# TES1.net
KiCad netlist of a schematic drawn in EAGLE
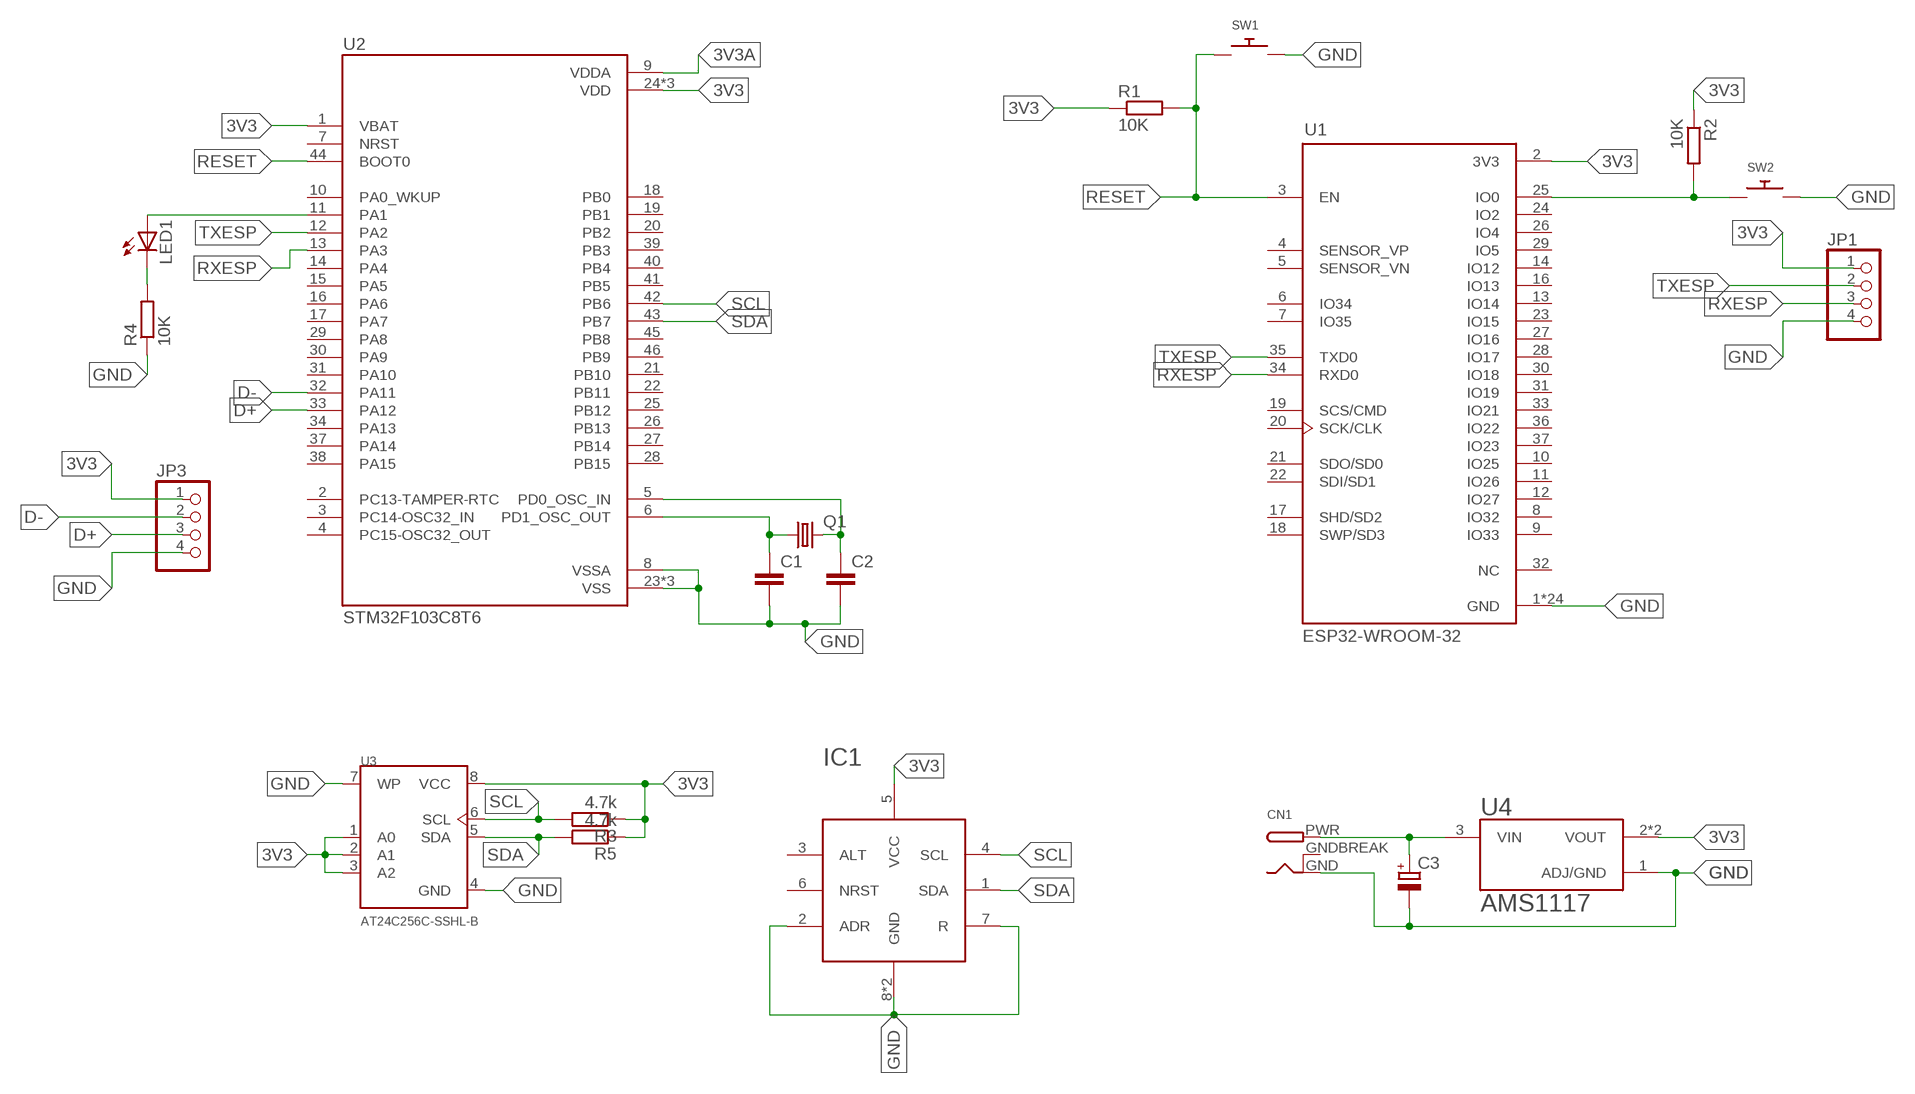
[diagram p0: schematic, sheet 1]

(export (version "E")
  (design (tool "Eeschema 10.0.6"))
  (components
    (comp (ref "C1")
      (value "C-EUC0805")
      (footprint "eagle-import:C0805")
      (libsource (lib "eagle-import") (part "C-EUC0805"))
    )
    (comp (ref "C2")
      (value "C-EUC0805")
      (footprint "eagle-import:C0805")
      (libsource (lib "eagle-import") (part "C-EUC0805"))
    )
    (comp (ref "C3")
      (value "CPOL-EU150CLZ-0810")
      (footprint "eagle-import:150CLZ-0810")
      (libsource (lib "eagle-import") (part "CPOL-EU150CLZ-0810"))
    )
    (comp (ref "CN1")
      (value "DCBARRELPTH")
      (footprint "eagle-import:DCJACK_2MM_PTH")
      (libsource (lib "eagle-import") (part "DCBARRELPTH"))
    )
    (comp (ref "IC1")
      (value "SHT31")
      (footprint "eagle-import:SON50P250X250X90-9T110X180N")
      (fields (field (name "MF") "Sensirion AG"))
      (libsource (lib "eagle-import") (part "SHT31"))
    )
    (comp (ref "JP1")
      (value "PINHD-1X4")
      (footprint "eagle-import:1X04")
      (libsource (lib "eagle-import") (part "PINHD-1X4"))
    )
    (comp (ref "JP3")
      (value "PINHD-1X4")
      (footprint "eagle-import:1X04")
      (libsource (lib "eagle-import") (part "PINHD-1X4"))
    )
    (comp (ref "LED1")
      (value "LEDCHIP-LED0805")
      (footprint "eagle-import:CHIP-LED0805")
      (libsource (lib "eagle-import") (part "LEDCHIP-LED0805"))
    )
    (comp (ref "Q1")
      (value "CRYSTALHC49U-V")
      (footprint "eagle-import:HC49U-V")
      (libsource (lib "eagle-import") (part "CRYSTALHC49U-V"))
    )
    (comp (ref "R1")
      (value "10K")
      (footprint "eagle-import:R0805")
      (libsource (lib "eagle-import") (part "R-EU_R0805"))
    )
    (comp (ref "R2")
      (value "10K")
      (footprint "eagle-import:R0805")
      (libsource (lib "eagle-import") (part "R-EU_R0805"))
    )
    (comp (ref "R3")
      (value "4.7k")
      (footprint "eagle-import:R0805")
      (libsource (lib "eagle-import") (part "R-EU_R0805"))
    )
    (comp (ref "R4")
      (value "10K")
      (footprint "eagle-import:R0805")
      (libsource (lib "eagle-import") (part "R-EU_R0805"))
    )
    (comp (ref "R5")
      (value "4.7k")
      (footprint "eagle-import:R0805")
      (libsource (lib "eagle-import") (part "R-EU_R0805"))
    )
    (comp (ref "SW1")
      (value "SWITCH_PUSHBUTTONC&K_KSS")
      (footprint "eagle-import:BTN_CK_KSS")
      (libsource (lib "eagle-import") (part "SWITCH_PUSHBUTTONC&K_KSS"))
    )
    (comp (ref "SW2")
      (value "SWITCH_PUSHBUTTONC&K_KSS")
      (footprint "eagle-import:BTN_CK_KSS")
      (libsource (lib "eagle-import") (part "SWITCH_PUSHBUTTONC&K_KSS"))
    )
    (comp (ref "U1")
      (value "ESP32-WROOM-32")
      (footprint "eagle-import:MODULE_ESP32-WROOM-32")
      (fields (field (name "MF") "Espressif Systems"))
      (libsource (lib "eagle-import") (part "ESP32-WROOM-32"))
    )
    (comp (ref "U2")
      (value "STM32F103C8T6")
      (footprint "eagle-import:QFP50P900X900X160-48N")
      (fields (field (name "MF") "STMicroelectronics"))
      (libsource (lib "eagle-import") (part "STM32F103C8T6"))
    )
    (comp (ref "U3")
      (value "AT24C256C-SSHL-B")
      (footprint "eagle-import:SOIC127P600X175-8N")
      (fields (field (name "MF") "Microchip"))
      (libsource (lib "eagle-import") (part "AT24C256C-SSHL-B"))
    )
    (comp (ref "U4")
      (value "AMS1117")
      (footprint "eagle-import:SOT229P700X180-4N")
      (fields (field (name "MF") "Advanced Monolithic Systems"))
      (libsource (lib "eagle-import") (part "AMS1117"))
    )
  )
  (nets
    (net (code "1") (name "/GNDBREAK") (class "Default")
      (node (ref "CN1") (pin "GNDBREAK") (pinfunction "GNDBREAK_GNDBREAK") (pintype "power_in"))
    )
    (net (code "2") (name "3V3") (class "Default")
      (node (ref "IC1") (pin "5") (pinfunction "VCC_5") (pintype "bidirectional"))
      (node (ref "JP1") (pin "1") (pinfunction "1_1") (pintype "passive"))
      (node (ref "JP3") (pin "1") (pinfunction "1_1") (pintype "passive"))
      (node (ref "R1") (pin "1") (pinfunction "1_1") (pintype "passive"))
      (node (ref "R2") (pin "1") (pinfunction "1_1") (pintype "passive"))
      (node (ref "R3") (pin "1") (pinfunction "1_1") (pintype "passive"))
      (node (ref "R5") (pin "1") (pinfunction "1_1") (pintype "passive"))
      (node (ref "U1") (pin "2") (pinfunction "3V3_2") (pintype "power_in"))
      (node (ref "U2") (pin "1") (pinfunction "VBAT_1") (pintype "bidirectional"))
      (node (ref "U2") (pin "24") (pinfunction "VDD_24") (pintype "power_in"))
      (node (ref "U2") (pin "36") (pinfunction "VDD_36") (pintype "power_in"))
      (node (ref "U2") (pin "48") (pinfunction "VDD_48") (pintype "power_in"))
      (node (ref "U3") (pin "1") (pinfunction "A0_1") (pintype "input"))
      (node (ref "U3") (pin "2") (pinfunction "A1_2") (pintype "input"))
      (node (ref "U3") (pin "3") (pinfunction "A2_3") (pintype "input"))
      (node (ref "U3") (pin "8") (pinfunction "VCC_8") (pintype "power_in"))
      (node (ref "U4") (pin "2") (pinfunction "VOUT_2") (pintype "output"))
      (node (ref "U4") (pin "4") (pinfunction "VOUT_4") (pintype "output"))
    )
    (net (code "3") (name "3V3A") (class "Default")
      (node (ref "U2") (pin "9") (pinfunction "VDDA_9") (pintype "power_in"))
    )
    (net (code "4") (name "D+") (class "Default")
      (node (ref "JP3") (pin "3") (pinfunction "3_3") (pintype "passive"))
      (node (ref "U2") (pin "33") (pinfunction "PA12_33") (pintype "bidirectional"))
    )
    (net (code "5") (name "D-") (class "Default")
      (node (ref "JP3") (pin "2") (pinfunction "2_2") (pintype "passive"))
      (node (ref "U2") (pin "32") (pinfunction "PA11_32") (pintype "bidirectional"))
    )
    (net (code "6") (name "GND") (class "Default")
      (node (ref "C1") (pin "2") (pinfunction "2_2") (pintype "passive"))
      (node (ref "C2") (pin "2") (pinfunction "2_2") (pintype "passive"))
      (node (ref "C3") (pin "-") (pinfunction "-_-") (pintype "passive"))
      (node (ref "CN1") (pin "GND") (pinfunction "GND_GND") (pintype "power_in"))
      (node (ref "IC1") (pin "2") (pinfunction "ADR_2") (pintype "bidirectional"))
      (node (ref "IC1") (pin "7") (pinfunction "R_7") (pintype "bidirectional"))
      (node (ref "IC1") (pin "8") (pinfunction "GND_8") (pintype "bidirectional"))
      (node (ref "IC1") (pin "9") (pinfunction "GND_9") (pintype "bidirectional"))
      (node (ref "JP1") (pin "4") (pinfunction "4_4") (pintype "passive"))
      (node (ref "JP3") (pin "4") (pinfunction "4_4") (pintype "passive"))
      (node (ref "R4") (pin "1") (pinfunction "1_1") (pintype "passive"))
      (node (ref "SW1") (pin "P$2") (pinfunction "P$2_P$2") (pintype "passive"))
      (node (ref "SW2") (pin "P$2") (pinfunction "P$2_P$2") (pintype "passive"))
      (node (ref "U1") (pin "1") (pinfunction "GND_1") (pintype "power_in"))
      (node (ref "U1") (pin "15") (pinfunction "GND_15") (pintype "power_in"))
      (node (ref "U1") (pin "38") (pinfunction "GND_38") (pintype "power_in"))
      (node (ref "U1") (pin "39_1") (pinfunction "GND_39_1") (pintype "power_in"))
      (node (ref "U1") (pin "39_10") (pinfunction "GND_39_10") (pintype "power_in"))
      (node (ref "U1") (pin "39_11") (pinfunction "GND_39_11") (pintype "power_in"))
      (node (ref "U1") (pin "39_12") (pinfunction "GND_39_12") (pintype "power_in"))
      (node (ref "U1") (pin "39_13") (pinfunction "GND_39_13") (pintype "power_in"))
      (node (ref "U1") (pin "39_14") (pinfunction "GND_39_14") (pintype "power_in"))
      (node (ref "U1") (pin "39_15") (pinfunction "GND_39_15") (pintype "power_in"))
      (node (ref "U1") (pin "39_16") (pinfunction "GND_39_16") (pintype "power_in"))
      (node (ref "U1") (pin "39_17") (pinfunction "GND_39_17") (pintype "power_in"))
      (node (ref "U1") (pin "39_18") (pinfunction "GND_39_18") (pintype "power_in"))
      (node (ref "U1") (pin "39_19") (pinfunction "GND_39_19") (pintype "power_in"))
      (node (ref "U1") (pin "39_2") (pinfunction "GND_39_2") (pintype "power_in"))
      (node (ref "U1") (pin "39_20") (pinfunction "GND_39_20") (pintype "power_in"))
      (node (ref "U1") (pin "39_21") (pinfunction "GND_39_21") (pintype "power_in"))
      (node (ref "U1") (pin "39_3") (pinfunction "GND_39_3") (pintype "power_in"))
      (node (ref "U1") (pin "39_4") (pinfunction "GND_39_4") (pintype "power_in"))
      (node (ref "U1") (pin "39_5") (pinfunction "GND_39_5") (pintype "power_in"))
      (node (ref "U1") (pin "39_6") (pinfunction "GND_39_6") (pintype "power_in"))
      (node (ref "U1") (pin "39_7") (pinfunction "GND_39_7") (pintype "power_in"))
      (node (ref "U1") (pin "39_8") (pinfunction "GND_39_8") (pintype "power_in"))
      (node (ref "U1") (pin "39_9") (pinfunction "GND_39_9") (pintype "power_in"))
      (node (ref "U2") (pin "23") (pinfunction "VSS_23") (pintype "power_in"))
      (node (ref "U2") (pin "35") (pinfunction "VSS_35") (pintype "power_in"))
      (node (ref "U2") (pin "47") (pinfunction "VSS_47") (pintype "power_in"))
      (node (ref "U2") (pin "8") (pinfunction "VSSA_8") (pintype "power_in"))
      (node (ref "U3") (pin "4") (pinfunction "GND_4") (pintype "power_in"))
      (node (ref "U3") (pin "7") (pinfunction "WP_7") (pintype "input"))
      (node (ref "U4") (pin "1") (pinfunction "ADJ/GND_1") (pintype "power_in"))
    )
    (net (code "7") (name "Net-(LED1-PadC)") (class "Default")
      (node (ref "LED1") (pin "C") (pinfunction "C_C") (pintype "passive"))
      (node (ref "R4") (pin "2") (pinfunction "2_2") (pintype "passive"))
    )
    (net (code "8") (name "Net-(U1-IO0)") (class "Default")
      (node (ref "R2") (pin "2") (pinfunction "2_2") (pintype "passive"))
      (node (ref "SW2") (pin "P$1") (pinfunction "P$1_P$1") (pintype "passive"))
      (node (ref "U1") (pin "25") (pinfunction "IO0_25") (pintype "bidirectional"))
    )
    (net (code "9") (name "Net-(U2-PA1)") (class "Default")
      (node (ref "LED1") (pin "A") (pinfunction "A_A") (pintype "passive"))
      (node (ref "U2") (pin "11") (pinfunction "PA1_11") (pintype "bidirectional"))
    )
    (net (code "10") (name "Net-(U2-PD0_OSC_IN)") (class "Default")
      (node (ref "C2") (pin "1") (pinfunction "1_1") (pintype "passive"))
      (node (ref "Q1") (pin "2") (pinfunction "2_2") (pintype "passive"))
      (node (ref "U2") (pin "5") (pinfunction "PD0_OSC_IN_5") (pintype "bidirectional"))
    )
    (net (code "11") (name "Net-(U2-PD1_OSC_OUT)") (class "Default")
      (node (ref "C1") (pin "1") (pinfunction "1_1") (pintype "passive"))
      (node (ref "Q1") (pin "1") (pinfunction "1_1") (pintype "passive"))
      (node (ref "U2") (pin "6") (pinfunction "PD1_OSC_OUT_6") (pintype "bidirectional"))
    )
    (net (code "12") (name "Net-(U4-VIN)") (class "Default")
      (node (ref "C3") (pin "+") (pinfunction "+_+") (pintype "passive"))
      (node (ref "CN1") (pin "PWR") (pinfunction "PWR_PWR") (pintype "power_in"))
      (node (ref "U4") (pin "3") (pinfunction "VIN_3") (pintype "input"))
    )
    (net (code "13") (name "RESET") (class "Default")
      (node (ref "R1") (pin "2") (pinfunction "2_2") (pintype "passive"))
      (node (ref "SW1") (pin "P$1") (pinfunction "P$1_P$1") (pintype "passive"))
      (node (ref "U1") (pin "3") (pinfunction "EN_3") (pintype "input"))
      (node (ref "U2") (pin "44") (pinfunction "BOOT0_44") (pintype "input"))
    )
    (net (code "14") (name "RXESP") (class "Default")
      (node (ref "JP1") (pin "3") (pinfunction "3_3") (pintype "passive"))
      (node (ref "U1") (pin "34") (pinfunction "RXD0_34") (pintype "bidirectional"))
      (node (ref "U2") (pin "13") (pinfunction "PA3_13") (pintype "bidirectional"))
    )
    (net (code "15") (name "SCL") (class "Default")
      (node (ref "IC1") (pin "4") (pinfunction "SCL_4") (pintype "bidirectional"))
      (node (ref "R3") (pin "2") (pinfunction "2_2") (pintype "passive"))
      (node (ref "U2") (pin "42") (pinfunction "PB6_42") (pintype "bidirectional"))
      (node (ref "U3") (pin "6") (pinfunction "SCL_6") (pintype "input"))
    )
    (net (code "16") (name "SDA") (class "Default")
      (node (ref "IC1") (pin "1") (pinfunction "SDA_1") (pintype "bidirectional"))
      (node (ref "R5") (pin "2") (pinfunction "2_2") (pintype "passive"))
      (node (ref "U2") (pin "43") (pinfunction "PB7_43") (pintype "bidirectional"))
      (node (ref "U3") (pin "5") (pinfunction "SDA_5") (pintype "bidirectional"))
    )
    (net (code "17") (name "TXESP") (class "Default")
      (node (ref "JP1") (pin "2") (pinfunction "2_2") (pintype "passive"))
      (node (ref "U1") (pin "35") (pinfunction "TXD0_35") (pintype "bidirectional"))
      (node (ref "U2") (pin "12") (pinfunction "PA2_12") (pintype "bidirectional"))
    )
    (net (code "18") (name "unconnected-(IC1-ALT-Pad3)") (class "Default")
      (node (ref "IC1") (pin "3") (pinfunction "ALT_3") (pintype "bidirectional"))
    )
    (net (code "19") (name "unconnected-(IC1-NRST-Pad6)") (class "Default")
      (node (ref "IC1") (pin "6") (pinfunction "NRST_6") (pintype "bidirectional"))
    )
    (net (code "20") (name "unconnected-(U1-IO2-Pad24)") (class "Default")
      (node (ref "U1") (pin "24") (pinfunction "IO2_24") (pintype "bidirectional"))
    )
    (net (code "21") (name "unconnected-(U1-IO4-Pad26)") (class "Default")
      (node (ref "U1") (pin "26") (pinfunction "IO4_26") (pintype "bidirectional"))
    )
    (net (code "22") (name "unconnected-(U1-IO5-Pad29)") (class "Default")
      (node (ref "U1") (pin "29") (pinfunction "IO5_29") (pintype "bidirectional"))
    )
    (net (code "23") (name "unconnected-(U1-IO12-Pad14)") (class "Default")
      (node (ref "U1") (pin "14") (pinfunction "IO12_14") (pintype "bidirectional"))
    )
    (net (code "24") (name "unconnected-(U1-IO13-Pad16)") (class "Default")
      (node (ref "U1") (pin "16") (pinfunction "IO13_16") (pintype "bidirectional"))
    )
    (net (code "25") (name "unconnected-(U1-IO14-Pad13)") (class "Default")
      (node (ref "U1") (pin "13") (pinfunction "IO14_13") (pintype "bidirectional"))
    )
    (net (code "26") (name "unconnected-(U1-IO15-Pad23)") (class "Default")
      (node (ref "U1") (pin "23") (pinfunction "IO15_23") (pintype "bidirectional"))
    )
    (net (code "27") (name "unconnected-(U1-IO16-Pad27)") (class "Default")
      (node (ref "U1") (pin "27") (pinfunction "IO16_27") (pintype "bidirectional"))
    )
    (net (code "28") (name "unconnected-(U1-IO17-Pad28)") (class "Default")
      (node (ref "U1") (pin "28") (pinfunction "IO17_28") (pintype "bidirectional"))
    )
    (net (code "29") (name "unconnected-(U1-IO18-Pad30)") (class "Default")
      (node (ref "U1") (pin "30") (pinfunction "IO18_30") (pintype "bidirectional"))
    )
    (net (code "30") (name "unconnected-(U1-IO19-Pad31)") (class "Default")
      (node (ref "U1") (pin "31") (pinfunction "IO19_31") (pintype "bidirectional"))
    )
    (net (code "31") (name "unconnected-(U1-IO21-Pad33)") (class "Default")
      (node (ref "U1") (pin "33") (pinfunction "IO21_33") (pintype "bidirectional"))
    )
    (net (code "32") (name "unconnected-(U1-IO22-Pad36)") (class "Default")
      (node (ref "U1") (pin "36") (pinfunction "IO22_36") (pintype "bidirectional"))
    )
    (net (code "33") (name "unconnected-(U1-IO23-Pad37)") (class "Default")
      (node (ref "U1") (pin "37") (pinfunction "IO23_37") (pintype "bidirectional"))
    )
    (net (code "34") (name "unconnected-(U1-IO25-Pad10)") (class "Default")
      (node (ref "U1") (pin "10") (pinfunction "IO25_10") (pintype "bidirectional"))
    )
    (net (code "35") (name "unconnected-(U1-IO26-Pad11)") (class "Default")
      (node (ref "U1") (pin "11") (pinfunction "IO26_11") (pintype "bidirectional"))
    )
    (net (code "36") (name "unconnected-(U1-IO27-Pad12)") (class "Default")
      (node (ref "U1") (pin "12") (pinfunction "IO27_12") (pintype "bidirectional"))
    )
    (net (code "37") (name "unconnected-(U1-IO32-Pad8)") (class "Default")
      (node (ref "U1") (pin "8") (pinfunction "IO32_8") (pintype "bidirectional"))
    )
    (net (code "38") (name "unconnected-(U1-IO33-Pad9)") (class "Default")
      (node (ref "U1") (pin "9") (pinfunction "IO33_9") (pintype "bidirectional"))
    )
    (net (code "39") (name "unconnected-(U1-IO34-Pad6)") (class "Default")
      (node (ref "U1") (pin "6") (pinfunction "IO34_6") (pintype "input"))
    )
    (net (code "40") (name "unconnected-(U1-IO35-Pad7)") (class "Default")
      (node (ref "U1") (pin "7") (pinfunction "IO35_7") (pintype "input"))
    )
    (net (code "41") (name "unconnected-(U1-NC-Pad32)") (class "Default")
      (node (ref "U1") (pin "32") (pinfunction "NC_32") (pintype "no_connect"))
    )
    (net (code "42") (name "unconnected-(U1-SCK{slash}CLK-Pad20)") (class "Default")
      (node (ref "U1") (pin "20") (pinfunction "SCK/CLK_20") (pintype "bidirectional"))
    )
    (net (code "43") (name "unconnected-(U1-SCS{slash}CMD-Pad19)") (class "Default")
      (node (ref "U1") (pin "19") (pinfunction "SCS/CMD_19") (pintype "bidirectional"))
    )
    (net (code "44") (name "unconnected-(U1-SDI{slash}SD1-Pad22)") (class "Default")
      (node (ref "U1") (pin "22") (pinfunction "SDI/SD1_22") (pintype "bidirectional"))
    )
    (net (code "45") (name "unconnected-(U1-SDO{slash}SD0-Pad21)") (class "Default")
      (node (ref "U1") (pin "21") (pinfunction "SDO/SD0_21") (pintype "bidirectional"))
    )
    (net (code "46") (name "unconnected-(U1-SENSOR_VN-Pad5)") (class "Default")
      (node (ref "U1") (pin "5") (pinfunction "SENSOR_VN_5") (pintype "input"))
    )
    (net (code "47") (name "unconnected-(U1-SENSOR_VP-Pad4)") (class "Default")
      (node (ref "U1") (pin "4") (pinfunction "SENSOR_VP_4") (pintype "input"))
    )
    (net (code "48") (name "unconnected-(U1-SHD{slash}SD2-Pad17)") (class "Default")
      (node (ref "U1") (pin "17") (pinfunction "SHD/SD2_17") (pintype "bidirectional"))
    )
    (net (code "49") (name "unconnected-(U1-SWP{slash}SD3-Pad18)") (class "Default")
      (node (ref "U1") (pin "18") (pinfunction "SWP/SD3_18") (pintype "bidirectional"))
    )
    (net (code "50") (name "unconnected-(U2-NRST-Pad7)") (class "Default")
      (node (ref "U2") (pin "7") (pinfunction "NRST_7") (pintype "input"))
    )
    (net (code "51") (name "unconnected-(U2-PA0_WKUP-Pad10)") (class "Default")
      (node (ref "U2") (pin "10") (pinfunction "PA0_WKUP_10") (pintype "bidirectional"))
    )
    (net (code "52") (name "unconnected-(U2-PA4-Pad14)") (class "Default")
      (node (ref "U2") (pin "14") (pinfunction "PA4_14") (pintype "bidirectional"))
    )
    (net (code "53") (name "unconnected-(U2-PA5-Pad15)") (class "Default")
      (node (ref "U2") (pin "15") (pinfunction "PA5_15") (pintype "bidirectional"))
    )
    (net (code "54") (name "unconnected-(U2-PA6-Pad16)") (class "Default")
      (node (ref "U2") (pin "16") (pinfunction "PA6_16") (pintype "bidirectional"))
    )
    (net (code "55") (name "unconnected-(U2-PA7-Pad17)") (class "Default")
      (node (ref "U2") (pin "17") (pinfunction "PA7_17") (pintype "bidirectional"))
    )
    (net (code "56") (name "unconnected-(U2-PA8-Pad29)") (class "Default")
      (node (ref "U2") (pin "29") (pinfunction "PA8_29") (pintype "bidirectional"))
    )
    (net (code "57") (name "unconnected-(U2-PA9-Pad30)") (class "Default")
      (node (ref "U2") (pin "30") (pinfunction "PA9_30") (pintype "bidirectional"))
    )
    (net (code "58") (name "unconnected-(U2-PA10-Pad31)") (class "Default")
      (node (ref "U2") (pin "31") (pinfunction "PA10_31") (pintype "bidirectional"))
    )
    (net (code "59") (name "unconnected-(U2-PA13-Pad34)") (class "Default")
      (node (ref "U2") (pin "34") (pinfunction "PA13_34") (pintype "bidirectional"))
    )
    (net (code "60") (name "unconnected-(U2-PA14-Pad37)") (class "Default")
      (node (ref "U2") (pin "37") (pinfunction "PA14_37") (pintype "bidirectional"))
    )
    (net (code "61") (name "unconnected-(U2-PA15-Pad38)") (class "Default")
      (node (ref "U2") (pin "38") (pinfunction "PA15_38") (pintype "bidirectional"))
    )
    (net (code "62") (name "unconnected-(U2-PB0-Pad18)") (class "Default")
      (node (ref "U2") (pin "18") (pinfunction "PB0_18") (pintype "bidirectional"))
    )
    (net (code "63") (name "unconnected-(U2-PB1-Pad19)") (class "Default")
      (node (ref "U2") (pin "19") (pinfunction "PB1_19") (pintype "bidirectional"))
    )
    (net (code "64") (name "unconnected-(U2-PB2-Pad20)") (class "Default")
      (node (ref "U2") (pin "20") (pinfunction "PB2_20") (pintype "bidirectional"))
    )
    (net (code "65") (name "unconnected-(U2-PB3-Pad39)") (class "Default")
      (node (ref "U2") (pin "39") (pinfunction "PB3_39") (pintype "bidirectional"))
    )
    (net (code "66") (name "unconnected-(U2-PB4-Pad40)") (class "Default")
      (node (ref "U2") (pin "40") (pinfunction "PB4_40") (pintype "bidirectional"))
    )
    (net (code "67") (name "unconnected-(U2-PB5-Pad41)") (class "Default")
      (node (ref "U2") (pin "41") (pinfunction "PB5_41") (pintype "bidirectional"))
    )
    (net (code "68") (name "unconnected-(U2-PB8-Pad45)") (class "Default")
      (node (ref "U2") (pin "45") (pinfunction "PB8_45") (pintype "bidirectional"))
    )
    (net (code "69") (name "unconnected-(U2-PB9-Pad46)") (class "Default")
      (node (ref "U2") (pin "46") (pinfunction "PB9_46") (pintype "bidirectional"))
    )
    (net (code "70") (name "unconnected-(U2-PB10-Pad21)") (class "Default")
      (node (ref "U2") (pin "21") (pinfunction "PB10_21") (pintype "bidirectional"))
    )
    (net (code "71") (name "unconnected-(U2-PB11-Pad22)") (class "Default")
      (node (ref "U2") (pin "22") (pinfunction "PB11_22") (pintype "bidirectional"))
    )
    (net (code "72") (name "unconnected-(U2-PB12-Pad25)") (class "Default")
      (node (ref "U2") (pin "25") (pinfunction "PB12_25") (pintype "bidirectional"))
    )
    (net (code "73") (name "unconnected-(U2-PB13-Pad26)") (class "Default")
      (node (ref "U2") (pin "26") (pinfunction "PB13_26") (pintype "bidirectional"))
    )
    (net (code "74") (name "unconnected-(U2-PB14-Pad27)") (class "Default")
      (node (ref "U2") (pin "27") (pinfunction "PB14_27") (pintype "bidirectional"))
    )
    (net (code "75") (name "unconnected-(U2-PB15-Pad28)") (class "Default")
      (node (ref "U2") (pin "28") (pinfunction "PB15_28") (pintype "bidirectional"))
    )
    (net (code "76") (name "unconnected-(U2-PC13-TAMPER-RTC-Pad2)") (class "Default")
      (node (ref "U2") (pin "2") (pinfunction "PC13-TAMPER-RTC_2") (pintype "bidirectional"))
    )
    (net (code "77") (name "unconnected-(U2-PC14-OSC32_IN-Pad3)") (class "Default")
      (node (ref "U2") (pin "3") (pinfunction "PC14-OSC32_IN_3") (pintype "bidirectional"))
    )
    (net (code "78") (name "unconnected-(U2-PC15-OSC32_OUT-Pad4)") (class "Default")
      (node (ref "U2") (pin "4") (pinfunction "PC15-OSC32_OUT_4") (pintype "bidirectional"))
    )
  )
)
